# DIN-Rail-In_V103.net
KiCad netlist of a schematic drawn in EAGLE
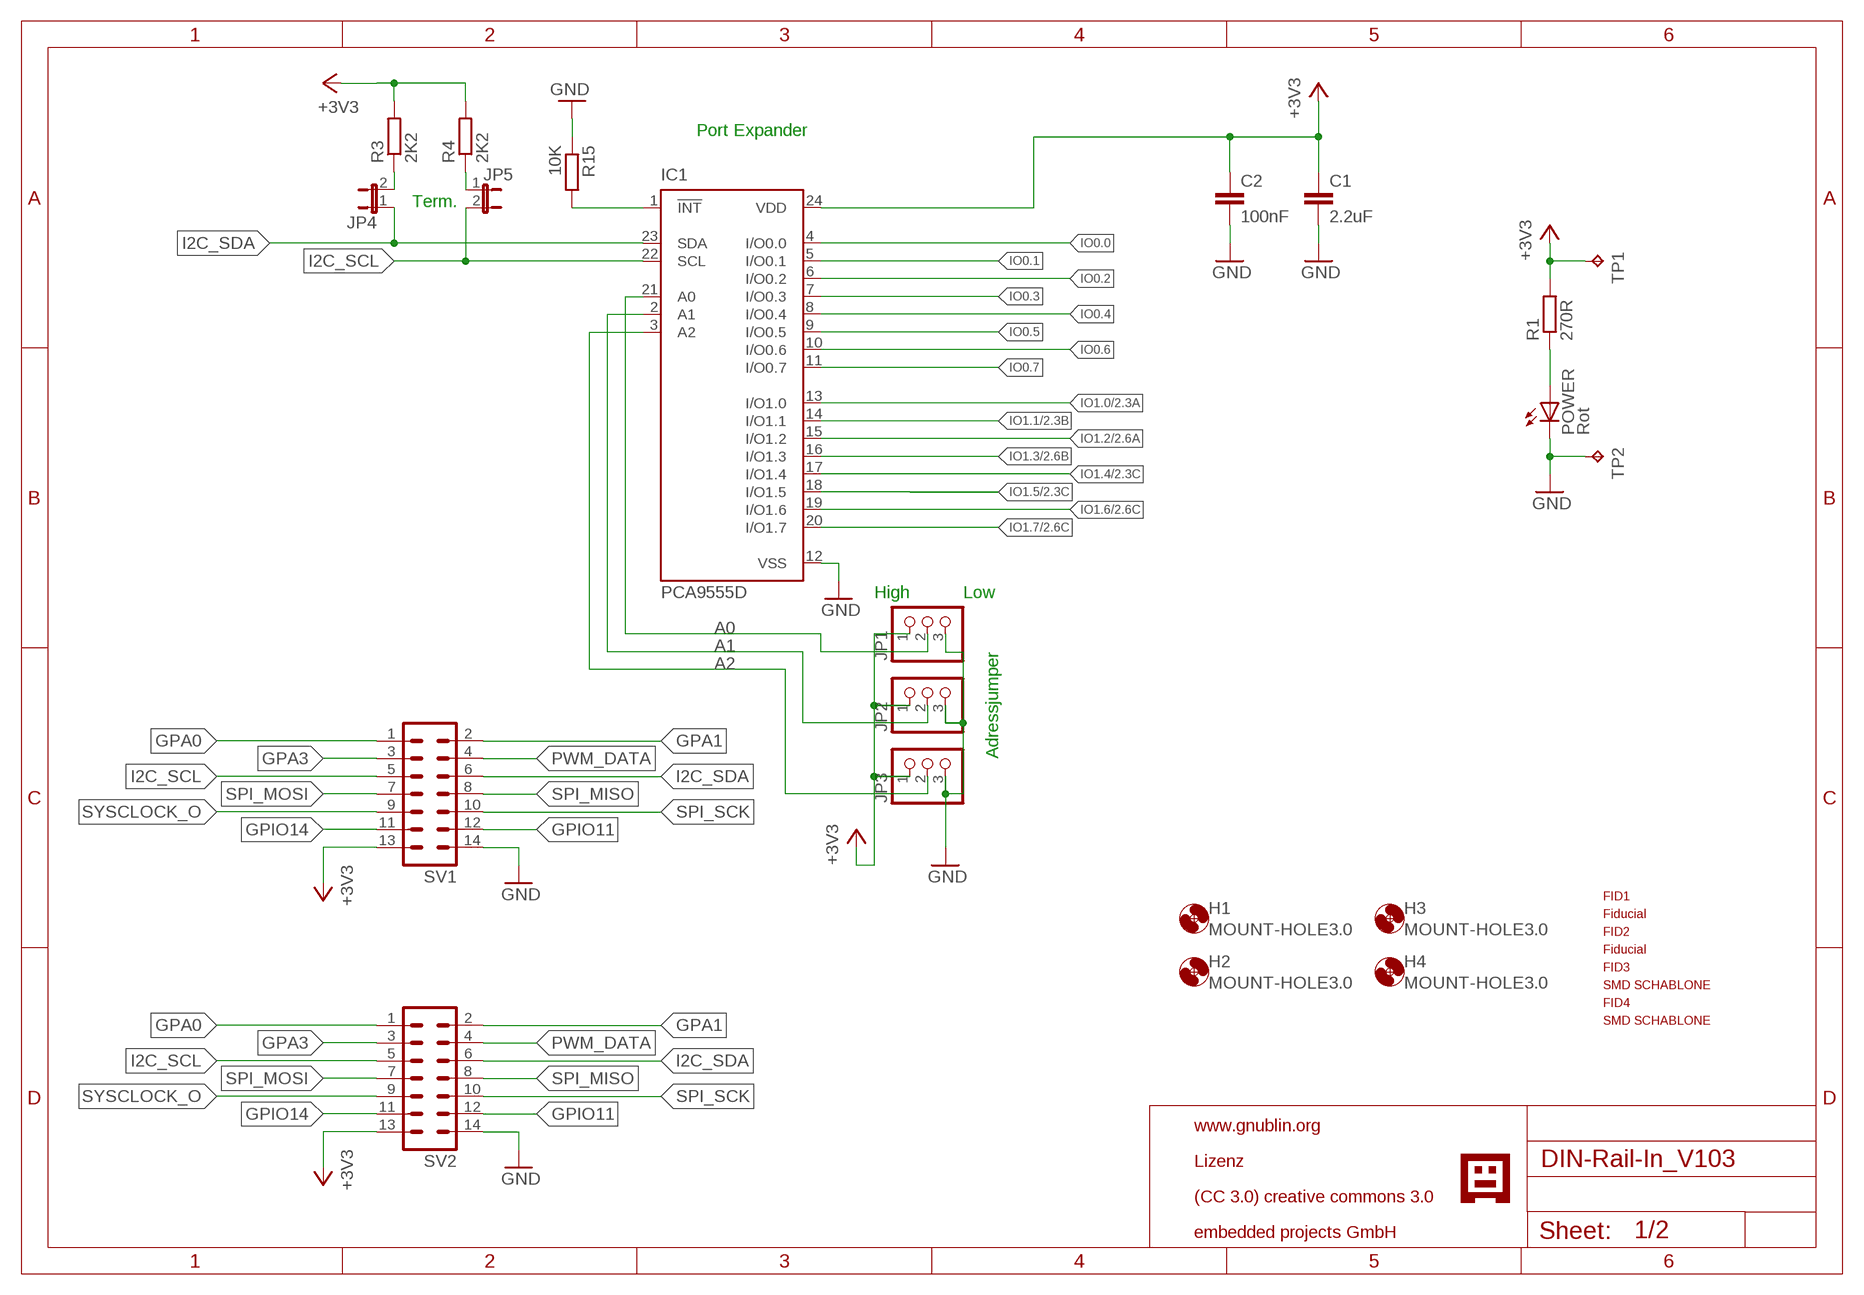
[diagram p0: schematic, sheet 1]
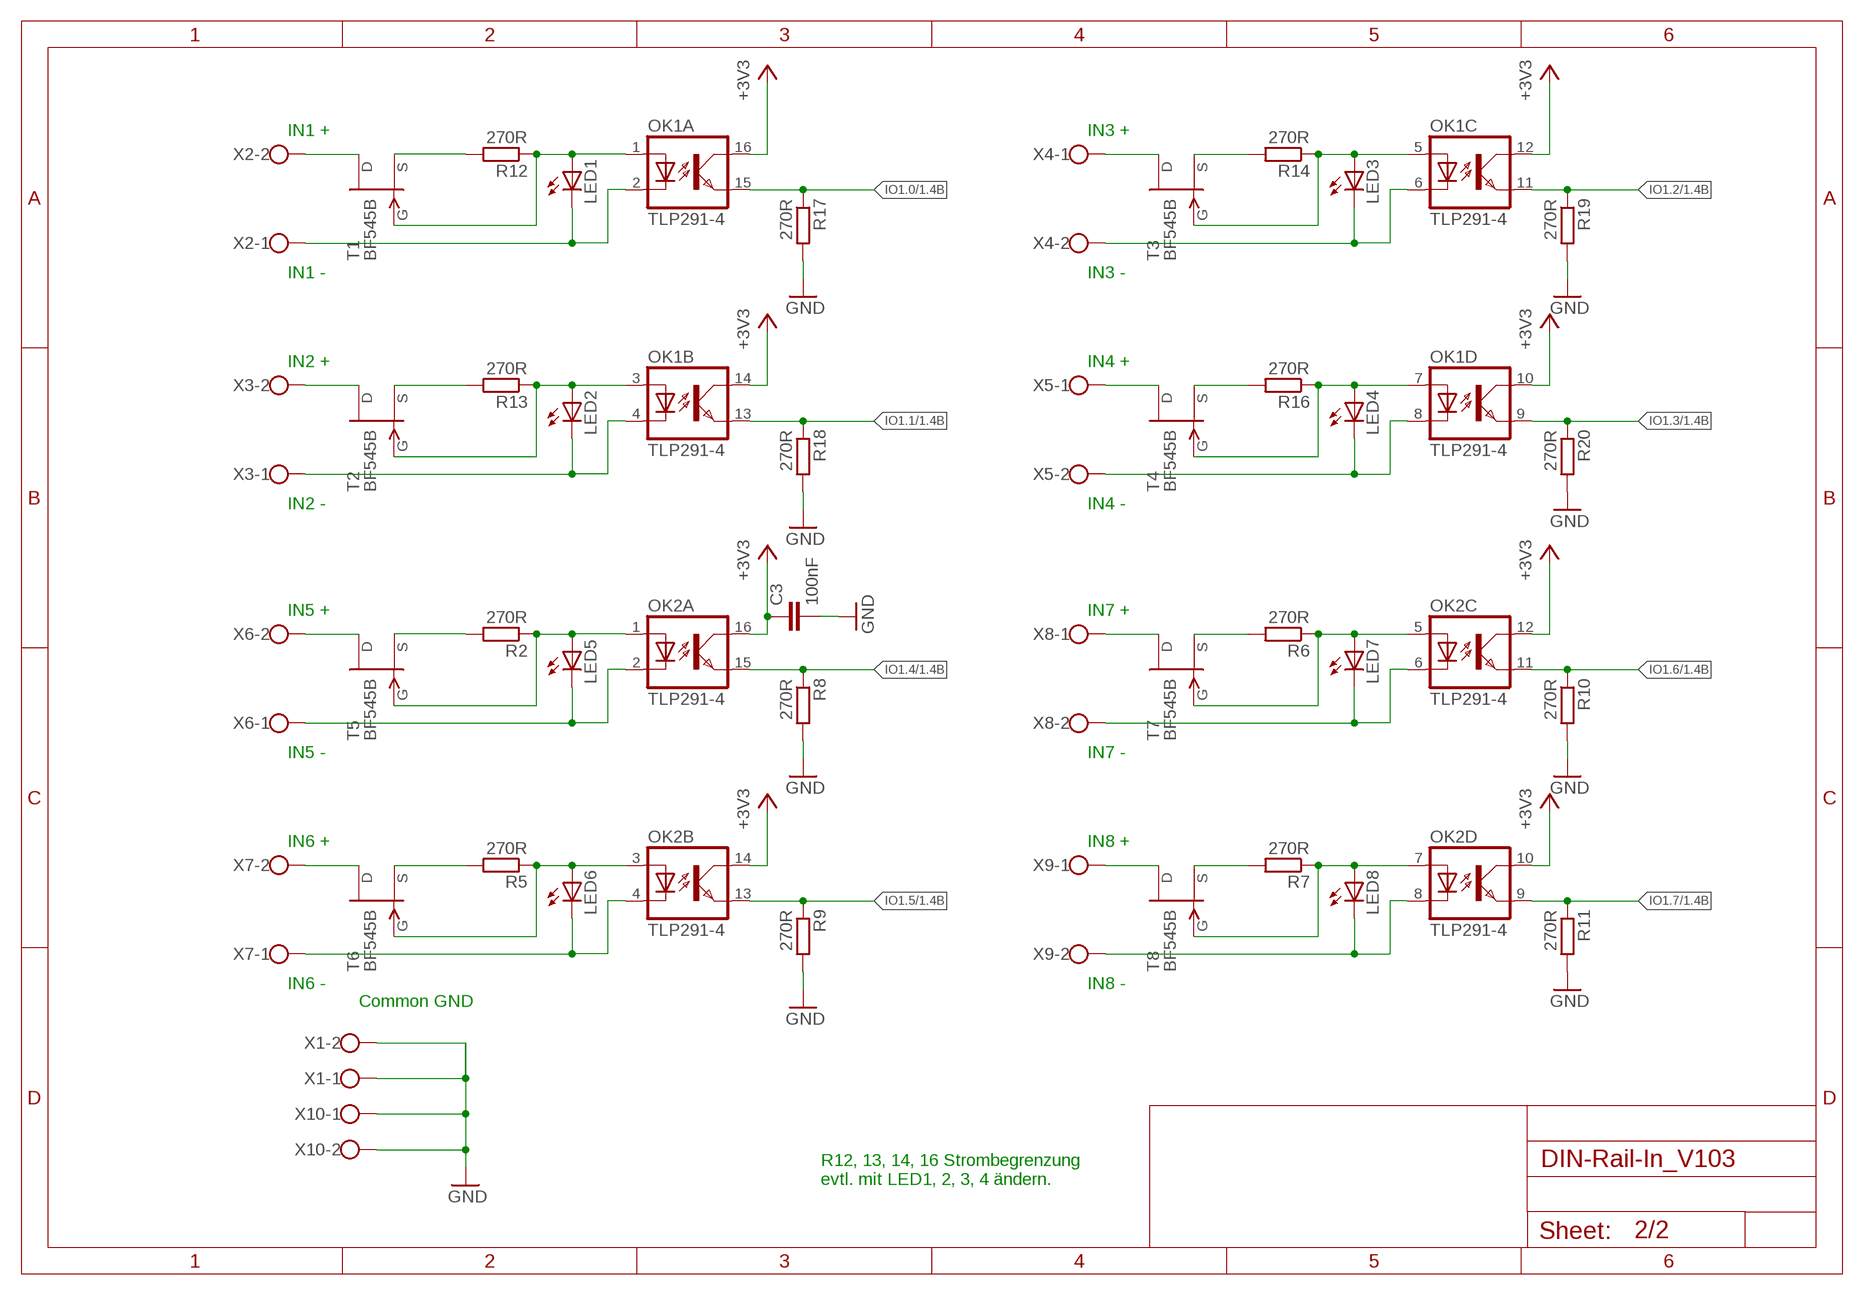
[diagram p1: schematic, sheet 2]

(export (version "E")
  (design (tool "Eeschema 10.0.6"))
  (components
    (comp (ref "C3")
      (value "100nF")
      (footprint "eagle-import:C0805")
      (libsource (lib "eagle-import") (part "C-EUC0805"))
    )
    (comp (ref "LED1")
      (value "LEDCHIPLED_0805")
      (footprint "eagle-import:CHIPLED_0805")
      (libsource (lib "eagle-import") (part "LEDCHIPLED_0805"))
    )
    (comp (ref "LED2")
      (value "LEDCHIPLED_0805")
      (footprint "eagle-import:CHIPLED_0805")
      (libsource (lib "eagle-import") (part "LEDCHIPLED_0805"))
    )
    (comp (ref "LED3")
      (value "LEDCHIPLED_0805")
      (footprint "eagle-import:CHIPLED_0805")
      (libsource (lib "eagle-import") (part "LEDCHIPLED_0805"))
    )
    (comp (ref "LED4")
      (value "LEDCHIPLED_0805")
      (footprint "eagle-import:CHIPLED_0805")
      (libsource (lib "eagle-import") (part "LEDCHIPLED_0805"))
    )
    (comp (ref "LED5")
      (value "LEDCHIPLED_0805")
      (footprint "eagle-import:CHIPLED_0805")
      (libsource (lib "eagle-import") (part "LEDCHIPLED_0805"))
    )
    (comp (ref "LED6")
      (value "LEDCHIPLED_0805")
      (footprint "eagle-import:CHIPLED_0805")
      (libsource (lib "eagle-import") (part "LEDCHIPLED_0805"))
    )
    (comp (ref "LED7")
      (value "LEDCHIPLED_0805")
      (footprint "eagle-import:CHIPLED_0805")
      (libsource (lib "eagle-import") (part "LEDCHIPLED_0805"))
    )
    (comp (ref "LED8")
      (value "LEDCHIPLED_0805")
      (footprint "eagle-import:CHIPLED_0805")
      (libsource (lib "eagle-import") (part "LEDCHIPLED_0805"))
    )
    (comp (ref "OK1")
      (value "TLP291-4")
      (footprint "eagle-import:MINI-FLAT-16")
      (libsource (lib "eagle-import") (part "TLP283-4"))
    )
    (comp (ref "OK2")
      (value "TLP291-4")
      (footprint "eagle-import:MINI-FLAT-16")
      (libsource (lib "eagle-import") (part "TLP283-4"))
    )
    (comp (ref "R2")
      (value "270R")
      (footprint "eagle-import:R0805")
      (libsource (lib "eagle-import") (part "R-EU_R0805"))
    )
    (comp (ref "R5")
      (value "270R")
      (footprint "eagle-import:R0805")
      (libsource (lib "eagle-import") (part "R-EU_R0805"))
    )
    (comp (ref "R6")
      (value "270R")
      (footprint "eagle-import:R0805")
      (libsource (lib "eagle-import") (part "R-EU_R0805"))
    )
    (comp (ref "R7")
      (value "270R")
      (footprint "eagle-import:R0805")
      (libsource (lib "eagle-import") (part "R-EU_R0805"))
    )
    (comp (ref "R8")
      (value "270R")
      (footprint "eagle-import:R0805")
      (libsource (lib "eagle-import") (part "R-EU_R0805"))
    )
    (comp (ref "R9")
      (value "270R")
      (footprint "eagle-import:R0805")
      (libsource (lib "eagle-import") (part "R-EU_R0805"))
    )
    (comp (ref "R10")
      (value "270R")
      (footprint "eagle-import:R0805")
      (libsource (lib "eagle-import") (part "R-EU_R0805"))
    )
    (comp (ref "R11")
      (value "270R")
      (footprint "eagle-import:R0805")
      (libsource (lib "eagle-import") (part "R-EU_R0805"))
    )
    (comp (ref "R12")
      (value "270R")
      (footprint "eagle-import:R0805")
      (libsource (lib "eagle-import") (part "R-EU_R0805"))
    )
    (comp (ref "R13")
      (value "270R")
      (footprint "eagle-import:R0805")
      (libsource (lib "eagle-import") (part "R-EU_R0805"))
    )
    (comp (ref "R14")
      (value "270R")
      (footprint "eagle-import:R0805")
      (libsource (lib "eagle-import") (part "R-EU_R0805"))
    )
    (comp (ref "R16")
      (value "270R")
      (footprint "eagle-import:R0805")
      (libsource (lib "eagle-import") (part "R-EU_R0805"))
    )
    (comp (ref "R17")
      (value "270R")
      (footprint "eagle-import:R0805")
      (libsource (lib "eagle-import") (part "R-EU_R0805"))
    )
    (comp (ref "R18")
      (value "270R")
      (footprint "eagle-import:R0805")
      (libsource (lib "eagle-import") (part "R-EU_R0805"))
    )
    (comp (ref "R19")
      (value "270R")
      (footprint "eagle-import:R0805")
      (libsource (lib "eagle-import") (part "R-EU_R0805"))
    )
    (comp (ref "R20")
      (value "270R")
      (footprint "eagle-import:R0805")
      (libsource (lib "eagle-import") (part "R-EU_R0805"))
    )
    (comp (ref "T1")
      (value "BF545B")
      (footprint "eagle-import:SOT-23")
      (libsource (lib "eagle-import") (part "BF545B"))
    )
    (comp (ref "T2")
      (value "BF545B")
      (footprint "eagle-import:SOT-23")
      (libsource (lib "eagle-import") (part "BF545B"))
    )
    (comp (ref "T3")
      (value "BF545B")
      (footprint "eagle-import:SOT-23")
      (libsource (lib "eagle-import") (part "BF545B"))
    )
    (comp (ref "T4")
      (value "BF545B")
      (footprint "eagle-import:SOT-23")
      (libsource (lib "eagle-import") (part "BF545B"))
    )
    (comp (ref "T5")
      (value "BF545B")
      (footprint "eagle-import:SOT-23")
      (libsource (lib "eagle-import") (part "BF545B"))
    )
    (comp (ref "T6")
      (value "BF545B")
      (footprint "eagle-import:SOT-23")
      (libsource (lib "eagle-import") (part "BF545B"))
    )
    (comp (ref "T7")
      (value "BF545B")
      (footprint "eagle-import:SOT-23")
      (libsource (lib "eagle-import") (part "BF545B"))
    )
    (comp (ref "T8")
      (value "BF545B")
      (footprint "eagle-import:SOT-23")
      (libsource (lib "eagle-import") (part "BF545B"))
    )
    (comp (ref "X1")
      (value "W237-02P")
      (footprint "eagle-import:W237-132")
      (libsource (lib "eagle-import") (part "W237-02P"))
    )
    (comp (ref "X2")
      (value "W237-02P")
      (footprint "eagle-import:W237-132")
      (libsource (lib "eagle-import") (part "W237-02P"))
    )
    (comp (ref "X3")
      (value "W237-02P")
      (footprint "eagle-import:W237-132")
      (libsource (lib "eagle-import") (part "W237-02P"))
    )
    (comp (ref "X4")
      (value "W237-02P")
      (footprint "eagle-import:W237-132")
      (libsource (lib "eagle-import") (part "W237-02P"))
    )
    (comp (ref "X5")
      (value "W237-02P")
      (footprint "eagle-import:W237-132")
      (libsource (lib "eagle-import") (part "W237-02P"))
    )
    (comp (ref "X6")
      (value "W237-02P")
      (footprint "eagle-import:W237-132")
      (libsource (lib "eagle-import") (part "W237-02P"))
    )
    (comp (ref "X7")
      (value "W237-02P")
      (footprint "eagle-import:W237-132")
      (libsource (lib "eagle-import") (part "W237-02P"))
    )
    (comp (ref "X8")
      (value "W237-02P")
      (footprint "eagle-import:W237-132")
      (libsource (lib "eagle-import") (part "W237-02P"))
    )
    (comp (ref "X9")
      (value "W237-02P")
      (footprint "eagle-import:W237-132")
      (libsource (lib "eagle-import") (part "W237-02P"))
    )
    (comp (ref "X10")
      (value "W237-02P")
      (footprint "eagle-import:W237-132")
      (libsource (lib "eagle-import") (part "W237-02P"))
    )
    (comp (ref "C1")
      (value "2.2uF")
      (footprint "eagle-import:C0805")
      (libsource (lib "eagle-import") (part "C-EUC0805"))
    )
    (comp (ref "C2")
      (value "100nF")
      (footprint "eagle-import:C0805")
      (libsource (lib "eagle-import") (part "C-EUC0805"))
    )
    (comp (ref "FID1")
      (value "PASSERMARKEN_FIDUCIAL")
      (footprint "eagle-import:PASSERMARKEN_FIDUCIAL")
      (libsource (lib "eagle-import") (part "PASSERMARKEN_FIDUCIAL"))
    )
    (comp (ref "FID2")
      (value "PASSERMARKEN_FIDUCIAL")
      (footprint "eagle-import:PASSERMARKEN_FIDUCIAL")
      (libsource (lib "eagle-import") (part "PASSERMARKEN_FIDUCIAL"))
    )
    (comp (ref "FID3")
      (value "PASSERMARKEN_FIDUCIAL")
      (footprint "eagle-import:PASSERMARKEN_FIDUCIAL")
      (libsource (lib "eagle-import") (part "SMDSCHABLONE_PASSERMARKEN_FIDUCIAL"))
    )
    (comp (ref "FID4")
      (value "PASSERMARKEN_FIDUCIAL")
      (footprint "eagle-import:PASSERMARKEN_FIDUCIAL")
      (libsource (lib "eagle-import") (part "SMDSCHABLONE_PASSERMARKEN_FIDUCIAL"))
    )
    (comp (ref "H1")
      (value "MOUNT-HOLE3.0")
      (footprint "eagle-import:3,0")
      (libsource (lib "eagle-import") (part "MOUNT-HOLE3.0"))
    )
    (comp (ref "H2")
      (value "MOUNT-HOLE3.0")
      (footprint "eagle-import:3,0")
      (libsource (lib "eagle-import") (part "MOUNT-HOLE3.0"))
    )
    (comp (ref "H3")
      (value "MOUNT-HOLE3.0")
      (footprint "eagle-import:3,0")
      (libsource (lib "eagle-import") (part "MOUNT-HOLE3.0"))
    )
    (comp (ref "H4")
      (value "MOUNT-HOLE3.0")
      (footprint "eagle-import:3,0")
      (libsource (lib "eagle-import") (part "MOUNT-HOLE3.0"))
    )
    (comp (ref "IC1")
      (value "PCA9555D")
      (footprint "eagle-import:SO24")
      (fields (field (name "MPN") "PCA9555DW") (field (name "OC_FARNELL") "8906076"))
      (libsource (lib "eagle-import") (part "PCA9555D"))
    )
    (comp (ref "JP1")
      (value "PINHD-1X3")
      (footprint "eagle-import:1X03")
      (libsource (lib "eagle-import") (part "PINHD-1X3"))
    )
    (comp (ref "JP2")
      (value "PINHD-1X3")
      (footprint "eagle-import:1X03")
      (libsource (lib "eagle-import") (part "PINHD-1X3"))
    )
    (comp (ref "JP3")
      (value "PINHD-1X3")
      (footprint "eagle-import:1X03")
      (libsource (lib "eagle-import") (part "PINHD-1X3"))
    )
    (comp (ref "JP4")
      (value "JP1E")
      (footprint "eagle-import:JP1")
      (libsource (lib "eagle-import") (part "JP1E"))
    )
    (comp (ref "JP5")
      (value "JP1E")
      (footprint "eagle-import:JP1")
      (libsource (lib "eagle-import") (part "JP1E"))
    )
    (comp (ref "POWER")
      (value "Rot")
      (footprint "eagle-import:CHIP-LED0805")
      (libsource (lib "eagle-import") (part "LEDCHIP-LED0805"))
    )
    (comp (ref "R1")
      (value "270R")
      (footprint "eagle-import:R0805")
      (libsource (lib "eagle-import") (part "R-EU_R0805"))
    )
    (comp (ref "R3")
      (value "2K2")
      (footprint "eagle-import:R0805")
      (libsource (lib "eagle-import") (part "R-EU_R0805"))
    )
    (comp (ref "R4")
      (value "2K2")
      (footprint "eagle-import:R0805")
      (libsource (lib "eagle-import") (part "R-EU_R0805"))
    )
    (comp (ref "R15")
      (value "10K")
      (footprint "eagle-import:R0805")
      (libsource (lib "eagle-import") (part "R-EU_R0805"))
    )
    (comp (ref "SV1")
      (value "ML14")
      (footprint "eagle-import:ML14")
      (libsource (lib "eagle-import") (part "ML14"))
    )
    (comp (ref "SV2")
      (value "ML14")
      (footprint "eagle-import:ML14")
      (libsource (lib "eagle-import") (part "ML14"))
    )
    (comp (ref "TP1")
      (value "TPB1,27")
      (footprint "eagle-import:B1,27")
      (libsource (lib "eagle-import") (part "TPB1,27"))
    )
    (comp (ref "TP2")
      (value "TPB1,27")
      (footprint "eagle-import:B1,27")
      (libsource (lib "eagle-import") (part "TPB1,27"))
    )
    (comp (ref "U$2")
      (value "GNUBLINLOGOSIEB")
      (footprint "eagle-import:GNUSIEBDRUCK")
      (libsource (lib "eagle-import") (part "GNUBLINLOGOSIEB"))
    )
  )
  (nets
    (net (code "1") (name "+3V3") (class "Default")
      (node (ref "C1") (pin "1") (pinfunction "1_1") (pintype "passive"))
      (node (ref "C2") (pin "1") (pinfunction "1_1") (pintype "passive"))
      (node (ref "C3") (pin "1") (pinfunction "1_1") (pintype "passive"))
      (node (ref "IC1") (pin "24") (pinfunction "VDD_24") (pintype "power_in"))
      (node (ref "JP1") (pin "1") (pinfunction "1_1") (pintype "passive"))
      (node (ref "JP2") (pin "1") (pinfunction "1_1") (pintype "passive"))
      (node (ref "JP3") (pin "1") (pinfunction "1_1") (pintype "passive"))
      (node (ref "OK1") (pin "10") (pinfunction "COL_10") (pintype "passive"))
      (node (ref "OK1") (pin "12") (pinfunction "COL_12") (pintype "passive"))
      (node (ref "OK1") (pin "14") (pinfunction "COL_14") (pintype "passive"))
      (node (ref "OK1") (pin "16") (pinfunction "COL_16") (pintype "passive"))
      (node (ref "OK2") (pin "10") (pinfunction "COL_10") (pintype "passive"))
      (node (ref "OK2") (pin "12") (pinfunction "COL_12") (pintype "passive"))
      (node (ref "OK2") (pin "14") (pinfunction "COL_14") (pintype "passive"))
      (node (ref "OK2") (pin "16") (pinfunction "COL_16") (pintype "passive"))
      (node (ref "R1") (pin "2") (pinfunction "2_2") (pintype "passive"))
      (node (ref "R3") (pin "2") (pinfunction "2_2") (pintype "passive"))
      (node (ref "R4") (pin "2") (pinfunction "2_2") (pintype "passive"))
      (node (ref "SV1") (pin "13") (pinfunction "13_13") (pintype "passive"))
      (node (ref "SV2") (pin "13") (pinfunction "13_13") (pintype "passive"))
      (node (ref "TP1") (pin "TP") (pinfunction "TP_TP") (pintype "input"))
    )
    (net (code "2") (name "A0") (class "Default")
      (node (ref "IC1") (pin "21") (pinfunction "A0_21") (pintype "input"))
      (node (ref "JP1") (pin "2") (pinfunction "2_2") (pintype "passive"))
    )
    (net (code "3") (name "A1") (class "Default")
      (node (ref "IC1") (pin "2") (pinfunction "A1_2") (pintype "input"))
      (node (ref "JP2") (pin "2") (pinfunction "2_2") (pintype "passive"))
    )
    (net (code "4") (name "A2") (class "Default")
      (node (ref "IC1") (pin "3") (pinfunction "A2_3") (pintype "input"))
      (node (ref "JP3") (pin "2") (pinfunction "2_2") (pintype "passive"))
    )
    (net (code "5") (name "GND") (class "Default")
      (node (ref "C1") (pin "2") (pinfunction "2_2") (pintype "passive"))
      (node (ref "C2") (pin "2") (pinfunction "2_2") (pintype "passive"))
      (node (ref "C3") (pin "2") (pinfunction "2_2") (pintype "passive"))
      (node (ref "IC1") (pin "12") (pinfunction "VSS_12") (pintype "power_in"))
      (node (ref "JP1") (pin "3") (pinfunction "3_3") (pintype "passive"))
      (node (ref "JP2") (pin "3") (pinfunction "3_3") (pintype "passive"))
      (node (ref "JP3") (pin "3") (pinfunction "3_3") (pintype "passive"))
      (node (ref "POWER") (pin "C") (pinfunction "C_C") (pintype "passive"))
      (node (ref "R10") (pin "2") (pinfunction "2_2") (pintype "passive"))
      (node (ref "R11") (pin "2") (pinfunction "2_2") (pintype "passive"))
      (node (ref "R15") (pin "1") (pinfunction "1_1") (pintype "passive"))
      (node (ref "R17") (pin "2") (pinfunction "2_2") (pintype "passive"))
      (node (ref "R18") (pin "2") (pinfunction "2_2") (pintype "passive"))
      (node (ref "R19") (pin "2") (pinfunction "2_2") (pintype "passive"))
      (node (ref "R20") (pin "2") (pinfunction "2_2") (pintype "passive"))
      (node (ref "R8") (pin "2") (pinfunction "2_2") (pintype "passive"))
      (node (ref "R9") (pin "2") (pinfunction "2_2") (pintype "passive"))
      (node (ref "SV1") (pin "14") (pinfunction "14_14") (pintype "passive"))
      (node (ref "SV2") (pin "14") (pinfunction "14_14") (pintype "passive"))
      (node (ref "TP2") (pin "TP") (pinfunction "TP_TP") (pintype "input"))
      (node (ref "X1") (pin "1") (pinfunction "KL_1") (pintype "passive"))
      (node (ref "X1") (pin "2") (pinfunction "KL_2") (pintype "passive"))
      (node (ref "X10") (pin "1") (pinfunction "KL_1") (pintype "passive"))
      (node (ref "X10") (pin "2") (pinfunction "KL_2") (pintype "passive"))
    )
    (net (code "6") (name "GPA0") (class "Default")
      (node (ref "SV1") (pin "1") (pinfunction "1_1") (pintype "passive"))
      (node (ref "SV2") (pin "1") (pinfunction "1_1") (pintype "passive"))
    )
    (net (code "7") (name "GPA1") (class "Default")
      (node (ref "SV1") (pin "2") (pinfunction "2_2") (pintype "passive"))
      (node (ref "SV2") (pin "2") (pinfunction "2_2") (pintype "passive"))
    )
    (net (code "8") (name "GPA3") (class "Default")
      (node (ref "SV1") (pin "3") (pinfunction "3_3") (pintype "passive"))
      (node (ref "SV2") (pin "3") (pinfunction "3_3") (pintype "passive"))
    )
    (net (code "9") (name "GPIO11") (class "Default")
      (node (ref "SV1") (pin "12") (pinfunction "12_12") (pintype "passive"))
      (node (ref "SV2") (pin "12") (pinfunction "12_12") (pintype "passive"))
    )
    (net (code "10") (name "GPIO14") (class "Default")
      (node (ref "SV1") (pin "11") (pinfunction "11_11") (pintype "passive"))
      (node (ref "SV2") (pin "11") (pinfunction "11_11") (pintype "passive"))
    )
    (net (code "11") (name "I2C_SCL") (class "Default")
      (node (ref "IC1") (pin "22") (pinfunction "SCL_22") (pintype "input"))
      (node (ref "JP5") (pin "2") (pinfunction "2_2") (pintype "passive"))
      (node (ref "SV1") (pin "5") (pinfunction "5_5") (pintype "passive"))
      (node (ref "SV2") (pin "5") (pinfunction "5_5") (pintype "passive"))
    )
    (net (code "12") (name "I2C_SDA") (class "Default")
      (node (ref "IC1") (pin "23") (pinfunction "SDA_23") (pintype "bidirectional"))
      (node (ref "JP4") (pin "1") (pinfunction "1_1") (pintype "passive"))
      (node (ref "SV1") (pin "6") (pinfunction "6_6") (pintype "passive"))
      (node (ref "SV2") (pin "6") (pinfunction "6_6") (pintype "passive"))
    )
    (net (code "13") (name "IO0.0") (class "Default")
      (node (ref "IC1") (pin "4") (pinfunction "I/O0.0_4") (pintype "bidirectional"))
    )
    (net (code "14") (name "IO0.1") (class "Default")
      (node (ref "IC1") (pin "5") (pinfunction "I/O0.1_5") (pintype "bidirectional"))
    )
    (net (code "15") (name "IO0.2") (class "Default")
      (node (ref "IC1") (pin "6") (pinfunction "I/O0.2_6") (pintype "bidirectional"))
    )
    (net (code "16") (name "IO0.3") (class "Default")
      (node (ref "IC1") (pin "7") (pinfunction "I/O0.3_7") (pintype "bidirectional"))
    )
    (net (code "17") (name "IO0.4") (class "Default")
      (node (ref "IC1") (pin "8") (pinfunction "I/O0.4_8") (pintype "bidirectional"))
    )
    (net (code "18") (name "IO0.5") (class "Default")
      (node (ref "IC1") (pin "9") (pinfunction "I/O0.5_9") (pintype "bidirectional"))
    )
    (net (code "19") (name "IO0.6") (class "Default")
      (node (ref "IC1") (pin "10") (pinfunction "I/O0.6_10") (pintype "bidirectional"))
    )
    (net (code "20") (name "IO0.7") (class "Default")
      (node (ref "IC1") (pin "11") (pinfunction "I/O0.7_11") (pintype "bidirectional"))
    )
    (net (code "21") (name "IO1.0") (class "Default")
      (node (ref "IC1") (pin "13") (pinfunction "I/O1.0_13") (pintype "bidirectional"))
      (node (ref "OK1") (pin "15") (pinfunction "EMIT_15") (pintype "passive"))
      (node (ref "R17") (pin "1") (pinfunction "1_1") (pintype "passive"))
    )
    (net (code "22") (name "IO1.1") (class "Default")
      (node (ref "IC1") (pin "14") (pinfunction "I/O1.1_14") (pintype "bidirectional"))
      (node (ref "OK1") (pin "13") (pinfunction "EMIT_13") (pintype "passive"))
      (node (ref "R18") (pin "1") (pinfunction "1_1") (pintype "passive"))
    )
    (net (code "23") (name "IO1.2") (class "Default")
      (node (ref "IC1") (pin "15") (pinfunction "I/O1.2_15") (pintype "bidirectional"))
      (node (ref "OK1") (pin "11") (pinfunction "EMIT_11") (pintype "passive"))
      (node (ref "R19") (pin "1") (pinfunction "1_1") (pintype "passive"))
    )
    (net (code "24") (name "IO1.3") (class "Default")
      (node (ref "IC1") (pin "16") (pinfunction "I/O1.3_16") (pintype "bidirectional"))
      (node (ref "OK1") (pin "9") (pinfunction "EMIT_9") (pintype "passive"))
      (node (ref "R20") (pin "1") (pinfunction "1_1") (pintype "passive"))
    )
    (net (code "25") (name "IO1.4") (class "Default")
      (node (ref "IC1") (pin "17") (pinfunction "I/O1.4_17") (pintype "bidirectional"))
      (node (ref "OK2") (pin "15") (pinfunction "EMIT_15") (pintype "passive"))
      (node (ref "R8") (pin "1") (pinfunction "1_1") (pintype "passive"))
    )
    (net (code "26") (name "IO1.5") (class "Default")
      (node (ref "IC1") (pin "18") (pinfunction "I/O1.5_18") (pintype "bidirectional"))
      (node (ref "OK2") (pin "13") (pinfunction "EMIT_13") (pintype "passive"))
      (node (ref "R9") (pin "1") (pinfunction "1_1") (pintype "passive"))
    )
    (net (code "27") (name "IO1.6") (class "Default")
      (node (ref "IC1") (pin "19") (pinfunction "I/O1.6_19") (pintype "bidirectional"))
      (node (ref "OK2") (pin "11") (pinfunction "EMIT_11") (pintype "passive"))
      (node (ref "R10") (pin "1") (pinfunction "1_1") (pintype "passive"))
    )
    (net (code "28") (name "IO1.7") (class "Default")
      (node (ref "IC1") (pin "20") (pinfunction "I/O1.7_20") (pintype "bidirectional"))
      (node (ref "OK2") (pin "9") (pinfunction "EMIT_9") (pintype "passive"))
      (node (ref "R11") (pin "1") (pinfunction "1_1") (pintype "passive"))
    )
    (net (code "29") (name "Net-(IC1-~{INT})") (class "Default")
      (node (ref "IC1") (pin "1") (pinfunction "~{INT}_1") (pintype "output"))
      (node (ref "R15") (pin "2") (pinfunction "2_2") (pintype "passive"))
    )
    (net (code "30") (name "Net-(JP4-Pad2)") (class "Default")
      (node (ref "JP4") (pin "2") (pinfunction "2_2") (pintype "passive"))
      (node (ref "R3") (pin "1") (pinfunction "1_1") (pintype "passive"))
    )
    (net (code "31") (name "Net-(JP5-Pad1)") (class "Default")
      (node (ref "JP5") (pin "1") (pinfunction "1_1") (pintype "passive"))
      (node (ref "R4") (pin "1") (pinfunction "1_1") (pintype "passive"))
    )
    (net (code "32") (name "Net-(OK1A-A)") (class "Default")
      (node (ref "LED1") (pin "A") (pinfunction "A_A") (pintype "passive"))
      (node (ref "OK1") (pin "1") (pinfunction "A_1") (pintype "passive"))
      (node (ref "R12") (pin "1") (pinfunction "1_1") (pintype "passive"))
      (node (ref "T1") (pin "3") (pinfunction "G_3") (pintype "passive"))
    )
    (net (code "33") (name "Net-(OK1A-C)") (class "Default")
      (node (ref "LED1") (pin "C") (pinfunction "C_C") (pintype "passive"))
      (node (ref "OK1") (pin "2") (pinfunction "C_2") (pintype "passive"))
      (node (ref "X2") (pin "1") (pinfunction "KL_1") (pintype "passive"))
    )
    (net (code "34") (name "Net-(OK1B-A)") (class "Default")
      (node (ref "LED2") (pin "A") (pinfunction "A_A") (pintype "passive"))
      (node (ref "OK1") (pin "3") (pinfunction "A_3") (pintype "passive"))
      (node (ref "R13") (pin "1") (pinfunction "1_1") (pintype "passive"))
      (node (ref "T2") (pin "3") (pinfunction "G_3") (pintype "passive"))
    )
    (net (code "35") (name "Net-(OK1B-C)") (class "Default")
      (node (ref "LED2") (pin "C") (pinfunction "C_C") (pintype "passive"))
      (node (ref "OK1") (pin "4") (pinfunction "C_4") (pintype "passive"))
      (node (ref "X3") (pin "1") (pinfunction "KL_1") (pintype "passive"))
    )
    (net (code "36") (name "Net-(OK1C-A)") (class "Default")
      (node (ref "LED3") (pin "A") (pinfunction "A_A") (pintype "passive"))
      (node (ref "OK1") (pin "5") (pinfunction "A_5") (pintype "passive"))
      (node (ref "R14") (pin "1") (pinfunction "1_1") (pintype "passive"))
      (node (ref "T3") (pin "3") (pinfunction "G_3") (pintype "passive"))
    )
    (net (code "37") (name "Net-(OK1C-C)") (class "Default")
      (node (ref "LED3") (pin "C") (pinfunction "C_C") (pintype "passive"))
      (node (ref "OK1") (pin "6") (pinfunction "C_6") (pintype "passive"))
      (node (ref "X4") (pin "2") (pinfunction "KL_2") (pintype "passive"))
    )
    (net (code "38") (name "Net-(OK1D-A)") (class "Default")
      (node (ref "LED4") (pin "A") (pinfunction "A_A") (pintype "passive"))
      (node (ref "OK1") (pin "7") (pinfunction "A_7") (pintype "passive"))
      (node (ref "R16") (pin "1") (pinfunction "1_1") (pintype "passive"))
      (node (ref "T4") (pin "3") (pinfunction "G_3") (pintype "passive"))
    )
    (net (code "39") (name "Net-(OK1D-C)") (class "Default")
      (node (ref "LED4") (pin "C") (pinfunction "C_C") (pintype "passive"))
      (node (ref "OK1") (pin "8") (pinfunction "C_8") (pintype "passive"))
      (node (ref "X5") (pin "2") (pinfunction "KL_2") (pintype "passive"))
    )
    (net (code "40") (name "Net-(OK2A-A)") (class "Default")
      (node (ref "LED5") (pin "A") (pinfunction "A_A") (pintype "passive"))
      (node (ref "OK2") (pin "1") (pinfunction "A_1") (pintype "passive"))
      (node (ref "R2") (pin "1") (pinfunction "1_1") (pintype "passive"))
      (node (ref "T5") (pin "3") (pinfunction "G_3") (pintype "passive"))
    )
    (net (code "41") (name "Net-(OK2A-C)") (class "Default")
      (node (ref "LED5") (pin "C") (pinfunction "C_C") (pintype "passive"))
      (node (ref "OK2") (pin "2") (pinfunction "C_2") (pintype "passive"))
      (node (ref "X6") (pin "1") (pinfunction "KL_1") (pintype "passive"))
    )
    (net (code "42") (name "Net-(OK2B-A)") (class "Default")
      (node (ref "LED6") (pin "A") (pinfunction "A_A") (pintype "passive"))
      (node (ref "OK2") (pin "3") (pinfunction "A_3") (pintype "passive"))
      (node (ref "R5") (pin "1") (pinfunction "1_1") (pintype "passive"))
      (node (ref "T6") (pin "3") (pinfunction "G_3") (pintype "passive"))
    )
    (net (code "43") (name "Net-(OK2B-C)") (class "Default")
      (node (ref "LED6") (pin "C") (pinfunction "C_C") (pintype "passive"))
      (node (ref "OK2") (pin "4") (pinfunction "C_4") (pintype "passive"))
      (node (ref "X7") (pin "1") (pinfunction "KL_1") (pintype "passive"))
    )
    (net (code "44") (name "Net-(OK2C-A)") (class "Default")
      (node (ref "LED7") (pin "A") (pinfunction "A_A") (pintype "passive"))
      (node (ref "OK2") (pin "5") (pinfunction "A_5") (pintype "passive"))
      (node (ref "R6") (pin "1") (pinfunction "1_1") (pintype "passive"))
      (node (ref "T7") (pin "3") (pinfunction "G_3") (pintype "passive"))
    )
    (net (code "45") (name "Net-(OK2C-C)") (class "Default")
      (node (ref "LED7") (pin "C") (pinfunction "C_C") (pintype "passive"))
      (node (ref "OK2") (pin "6") (pinfunction "C_6") (pintype "passive"))
      (node (ref "X8") (pin "2") (pinfunction "KL_2") (pintype "passive"))
    )
    (net (code "46") (name "Net-(OK2D-A)") (class "Default")
      (node (ref "LED8") (pin "A") (pinfunction "A_A") (pintype "passive"))
      (node (ref "OK2") (pin "7") (pinfunction "A_7") (pintype "passive"))
      (node (ref "R7") (pin "1") (pinfunction "1_1") (pintype "passive"))
      (node (ref "T8") (pin "3") (pinfunction "G_3") (pintype "passive"))
    )
    (net (code "47") (name "Net-(OK2D-C)") (class "Default")
      (node (ref "LED8") (pin "C") (pinfunction "C_C") (pintype "passive"))
      (node (ref "OK2") (pin "8") (pinfunction "C_8") (pintype "passive"))
      (node (ref "X9") (pin "2") (pinfunction "KL_2") (pintype "passive"))
    )
    (net (code "48") (name "Net-(POWER-PadA)") (class "Default")
      (node (ref "POWER") (pin "A") (pinfunction "A_A") (pintype "passive"))
      (node (ref "R1") (pin "1") (pinfunction "1_1") (pintype "passive"))
    )
    (net (code "49") (name "Net-(T1-D)") (class "Default")
      (node (ref "T1") (pin "2") (pinfunction "D_2") (pintype "passive"))
      (node (ref "X2") (pin "2") (pinfunction "KL_2") (pintype "passive"))
    )
    (net (code "50") (name "Net-(T1-S)") (class "Default")
      (node (ref "R12") (pin "2") (pinfunction "2_2") (pintype "passive"))
      (node (ref "T1") (pin "1") (pinfunction "S_1") (pintype "passive"))
    )
    (net (code "51") (name "Net-(T2-D)") (class "Default")
      (node (ref "T2") (pin "2") (pinfunction "D_2") (pintype "passive"))
      (node (ref "X3") (pin "2") (pinfunction "KL_2") (pintype "passive"))
    )
    (net (code "52") (name "Net-(T2-S)") (class "Default")
      (node (ref "R13") (pin "2") (pinfunction "2_2") (pintype "passive"))
      (node (ref "T2") (pin "1") (pinfunction "S_1") (pintype "passive"))
    )
    (net (code "53") (name "Net-(T3-D)") (class "Default")
      (node (ref "T3") (pin "2") (pinfunction "D_2") (pintype "passive"))
      (node (ref "X4") (pin "1") (pinfunction "KL_1") (pintype "passive"))
    )
    (net (code "54") (name "Net-(T3-S)") (class "Default")
      (node (ref "R14") (pin "2") (pinfunction "2_2") (pintype "passive"))
      (node (ref "T3") (pin "1") (pinfunction "S_1") (pintype "passive"))
    )
    (net (code "55") (name "Net-(T4-D)") (class "Default")
      (node (ref "T4") (pin "2") (pinfunction "D_2") (pintype "passive"))
      (node (ref "X5") (pin "1") (pinfunction "KL_1") (pintype "passive"))
    )
    (net (code "56") (name "Net-(T4-S)") (class "Default")
      (node (ref "R16") (pin "2") (pinfunction "2_2") (pintype "passive"))
      (node (ref "T4") (pin "1") (pinfunction "S_1") (pintype "passive"))
    )
    (net (code "57") (name "Net-(T5-D)") (class "Default")
      (node (ref "T5") (pin "2") (pinfunction "D_2") (pintype "passive"))
      (node (ref "X6") (pin "2") (pinfunction "KL_2") (pintype "passive"))
    )
    (net (code "58") (name "Net-(T5-S)") (class "Default")
      (node (ref "R2") (pin "2") (pinfunction "2_2") (pintype "passive"))
      (node (ref "T5") (pin "1") (pinfunction "S_1") (pintype "passive"))
    )
    (net (code "59") (name "Net-(T6-D)") (class "Default")
      (node (ref "T6") (pin "2") (pinfunction "D_2") (pintype "passive"))
      (node (ref "X7") (pin "2") (pinfunction "KL_2") (pintype "passive"))
    )
    (net (code "60") (name "Net-(T6-S)") (class "Default")
      (node (ref "R5") (pin "2") (pinfunction "2_2") (pintype "passive"))
      (node (ref "T6") (pin "1") (pinfunction "S_1") (pintype "passive"))
    )
    (net (code "61") (name "Net-(T7-D)") (class "Default")
      (node (ref "T7") (pin "2") (pinfunction "D_2") (pintype "passive"))
      (node (ref "X8") (pin "1") (pinfunction "KL_1") (pintype "passive"))
    )
    (net (code "62") (name "Net-(T7-S)") (class "Default")
      (node (ref "R6") (pin "2") (pinfunction "2_2") (pintype "passive"))
      (node (ref "T7") (pin "1") (pinfunction "S_1") (pintype "passive"))
    )
    (net (code "63") (name "Net-(T8-D)") (class "Default")
      (node (ref "T8") (pin "2") (pinfunction "D_2") (pintype "passive"))
      (node (ref "X9") (pin "1") (pinfunction "KL_1") (pintype "passive"))
    )
    (net (code "64") (name "Net-(T8-S)") (class "Default")
      (node (ref "R7") (pin "2") (pinfunction "2_2") (pintype "passive"))
      (node (ref "T8") (pin "1") (pinfunction "S_1") (pintype "passive"))
    )
    (net (code "65") (name "PWM_DATA") (class "Default")
      (node (ref "SV1") (pin "4") (pinfunction "4_4") (pintype "passive"))
      (node (ref "SV2") (pin "4") (pinfunction "4_4") (pintype "passive"))
    )
    (net (code "66") (name "SPI_MISO") (class "Default")
      (node (ref "SV1") (pin "8") (pinfunction "8_8") (pintype "passive"))
      (node (ref "SV2") (pin "8") (pinfunction "8_8") (pintype "passive"))
    )
    (net (code "67") (name "SPI_MOSI") (class "Default")
      (node (ref "SV1") (pin "7") (pinfunction "7_7") (pintype "passive"))
      (node (ref "SV2") (pin "7") (pinfunction "7_7") (pintype "passive"))
    )
    (net (code "68") (name "SPI_SCK") (class "Default")
      (node (ref "SV1") (pin "10") (pinfunction "10_10") (pintype "passive"))
      (node (ref "SV2") (pin "10") (pinfunction "10_10") (pintype "passive"))
    )
    (net (code "69") (name "SYSCLOCK_O") (class "Default")
      (node (ref "SV1") (pin "9") (pinfunction "9_9") (pintype "passive"))
      (node (ref "SV2") (pin "9") (pinfunction "9_9") (pintype "passive"))
    )
  )
)
